# iot_demo_mote.net
KiCad netlist of a schematic drawn in EAGLE
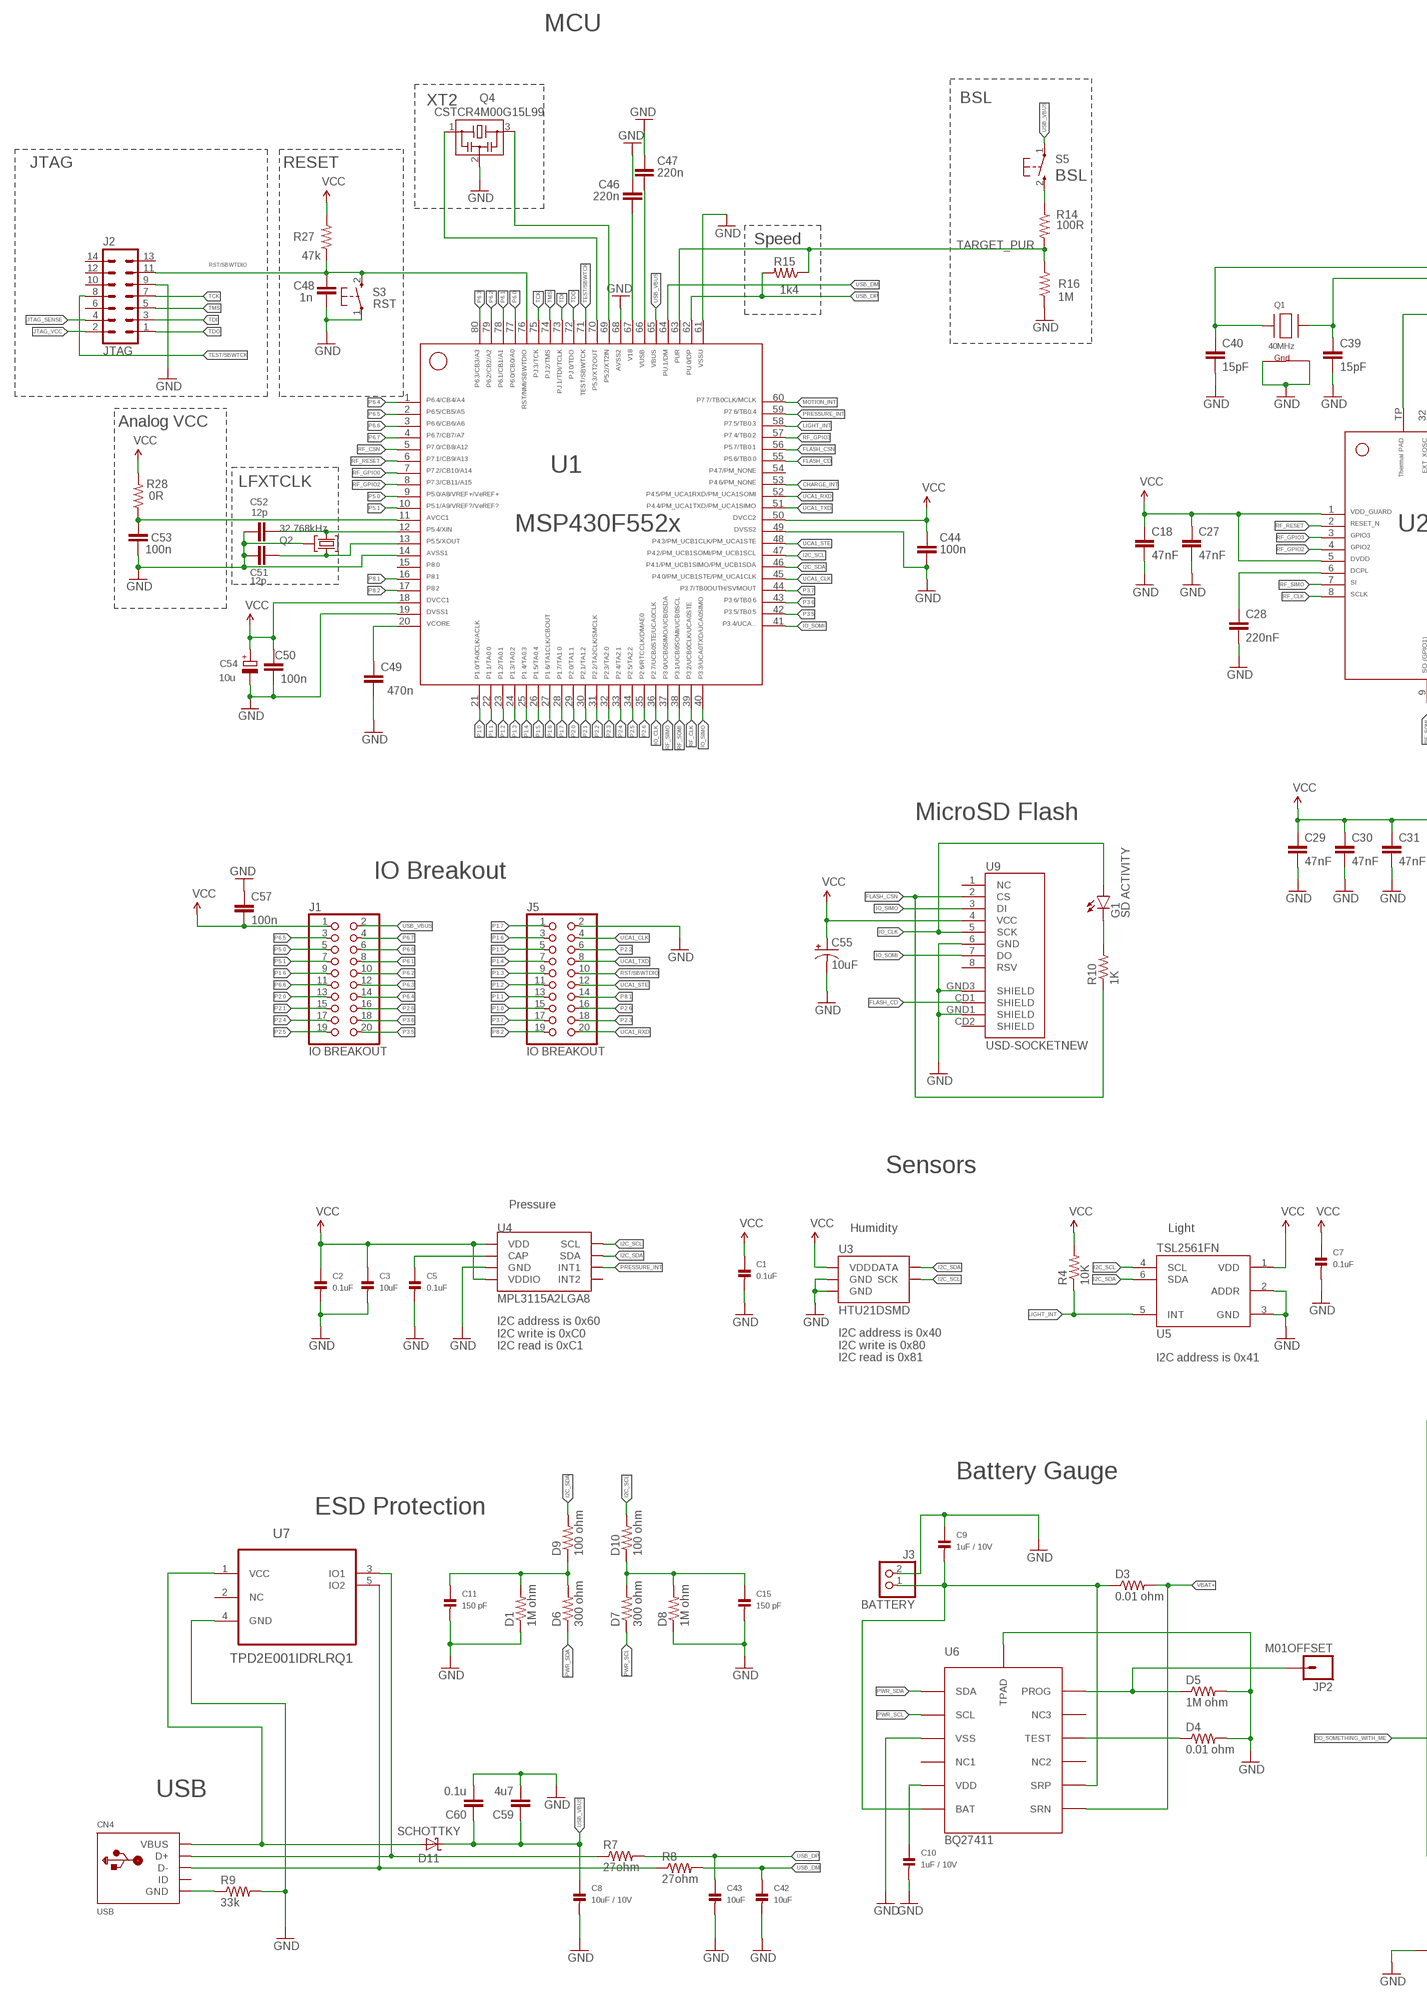
[diagram p0: schematic, sheet 1, part 1 of 2]
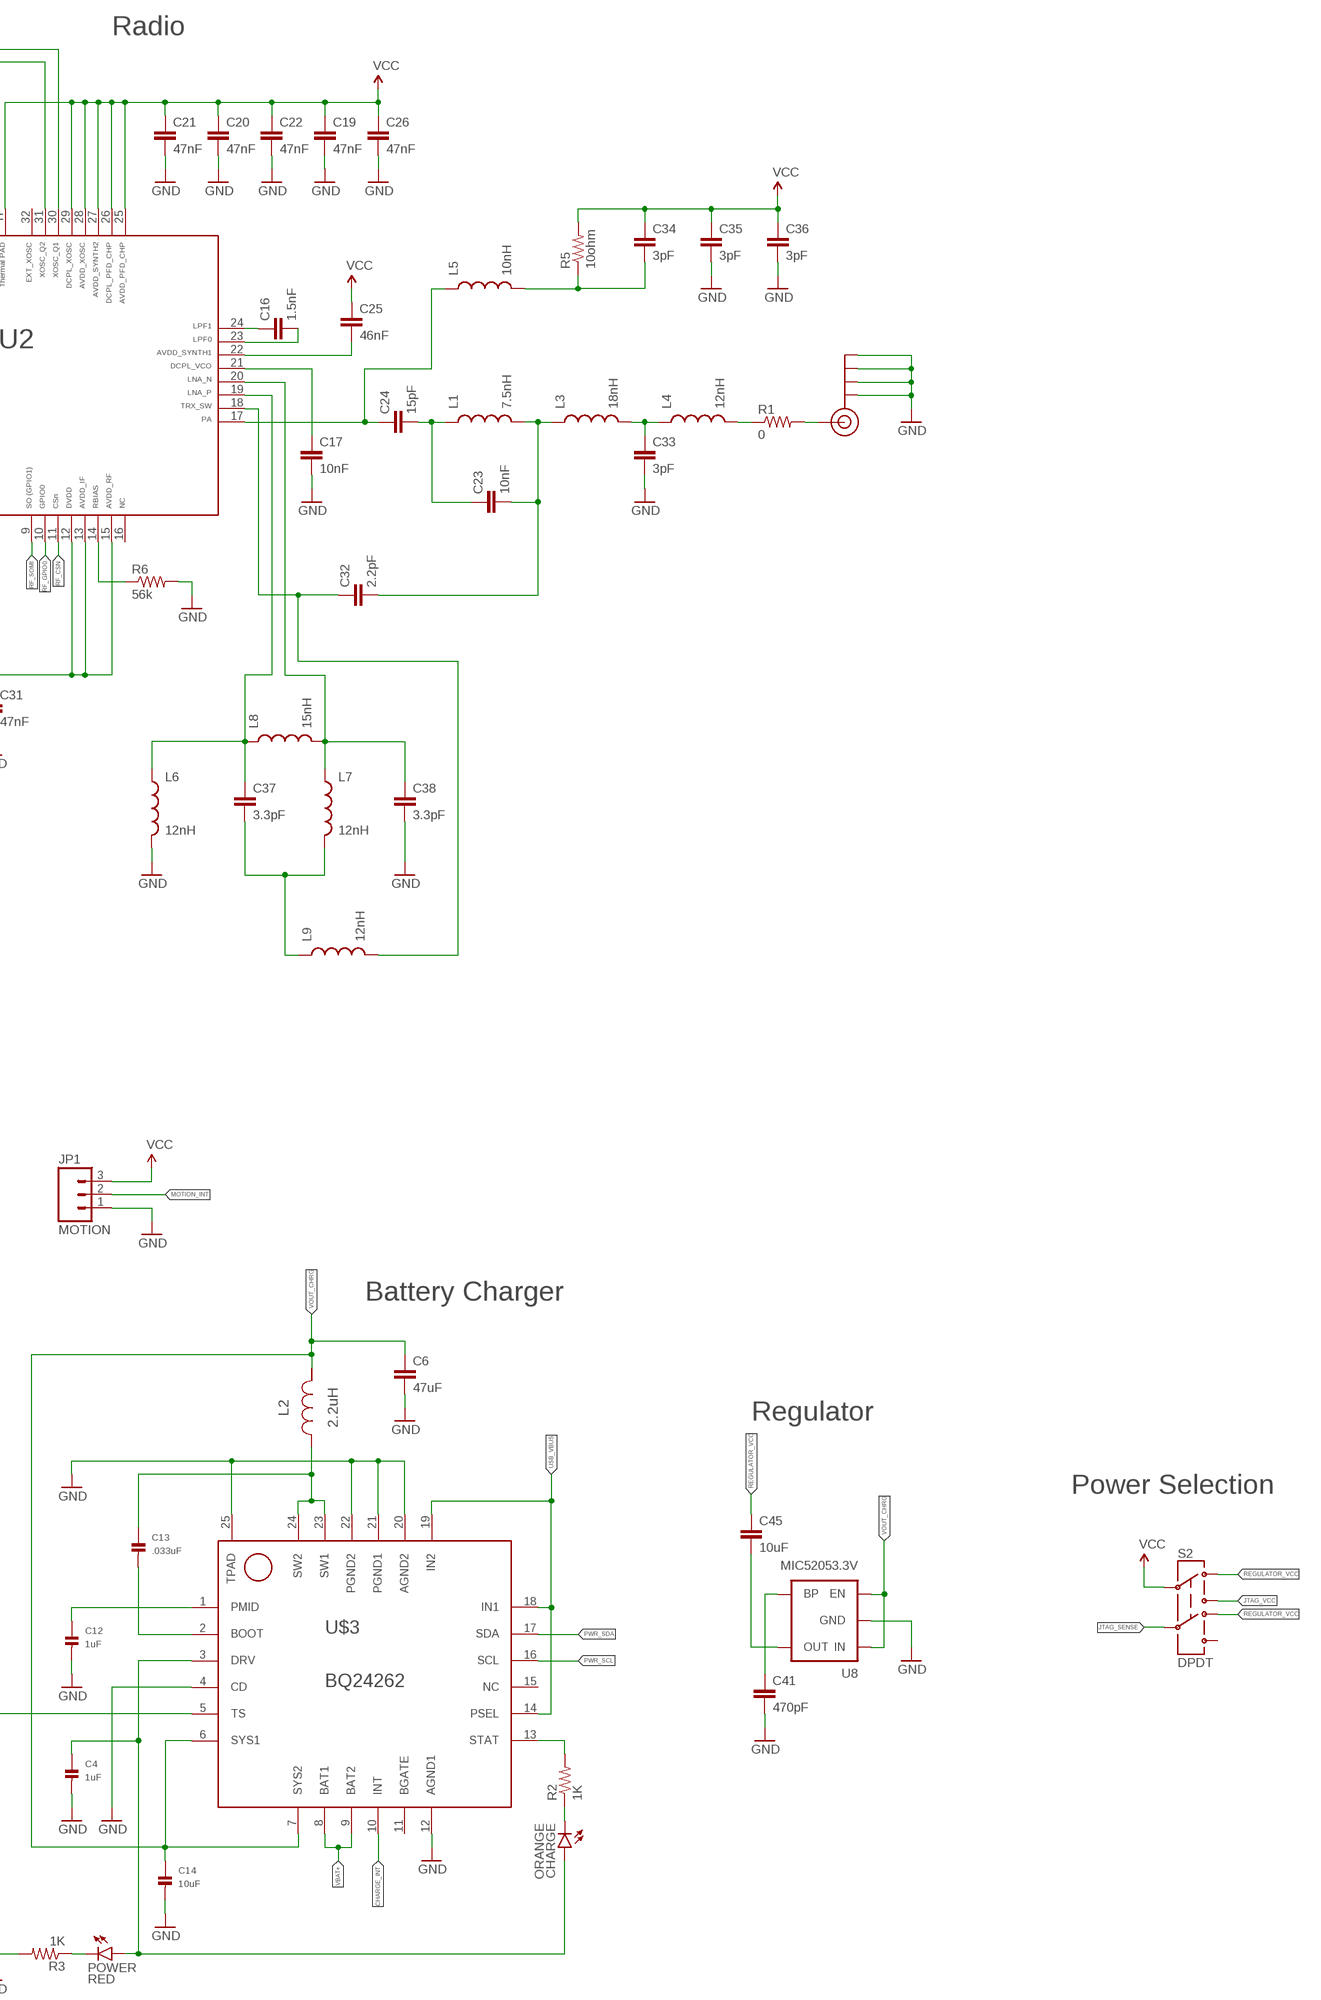
[diagram p1: schematic, sheet 1, part 2 of 2]

(export (version "E")
  (design (tool "Eeschema 10.0.6"))
  (components
    (comp (ref "C1")
      (value "0.1uF")
      (footprint "eagle-import:0603")
      (fields (field (name "MPN") "0603YC104JAT2A"))
      (libsource (lib "eagle-import") (part "CAP_CERAMIC0603"))
    )
    (comp (ref "C2")
      (value "0.1uF")
      (footprint "eagle-import:0603")
      (fields (field (name "MPN") "0603YC104JAT2A"))
      (libsource (lib "eagle-import") (part "CAP_CERAMIC0603"))
    )
    (comp (ref "C3")
      (value "10uF")
      (footprint "eagle-import:0603")
      (fields (field (name "MPN") "06035A100FAT2A"))
      (libsource (lib "eagle-import") (part "CAP_CERAMIC0603"))
    )
    (comp (ref "C4")
      (value "1uF")
      (footprint "eagle-import:0603")
      (fields (field (name "MPN") "06035A100FAT2A"))
      (libsource (lib "eagle-import") (part "CAP_CERAMIC0603"))
    )
    (comp (ref "C5")
      (value "0.1uF")
      (footprint "eagle-import:0603")
      (fields (field (name "MPN") "0603YC104JAT2A"))
      (libsource (lib "eagle-import") (part "CAP_CERAMIC0603"))
    )
    (comp (ref "C6")
      (value "47uF")
      (footprint "eagle-import:0402-CAP")
      (fields (field (name "MPN") "06035A100FAT2A"))
      (libsource (lib "eagle-import") (part "CAP0402-CAP"))
    )
    (comp (ref "C7")
      (value "0.1uF")
      (footprint "eagle-import:0603")
      (fields (field (name "MPN") "0603YC104JAT2A"))
      (libsource (lib "eagle-import") (part "CAP_CERAMIC0603"))
    )
    (comp (ref "C8")
      (value "10uF / 10V")
      (footprint "eagle-import:0603")
      (fields (field (name "MPN") "06035A100FAT2A"))
      (libsource (lib "eagle-import") (part "CAP_CERAMIC0603"))
    )
    (comp (ref "C9")
      (value "1uF / 10V")
      (footprint "eagle-import:0603")
      (fields (field (name "MPN") "06035A100FAT2A"))
      (libsource (lib "eagle-import") (part "CAP_CERAMIC0603"))
    )
    (comp (ref "C10")
      (value "1uF / 10V")
      (footprint "eagle-import:0603")
      (fields (field (name "MPN") "06035A100FAT2A"))
      (libsource (lib "eagle-import") (part "CAP_CERAMIC0603"))
    )
    (comp (ref "C11")
      (value "150 pF")
      (footprint "eagle-import:0603")
      (fields (field (name "MPN") "06035A100FAT2A"))
      (libsource (lib "eagle-import") (part "CAP_CERAMIC0603"))
    )
    (comp (ref "C12")
      (value "1uF")
      (footprint "eagle-import:0603")
      (fields (field (name "MPN") "06035A100FAT2A"))
      (libsource (lib "eagle-import") (part "CAP_CERAMIC0603"))
    )
    (comp (ref "C13")
      (value ".033uF")
      (footprint "eagle-import:0603")
      (fields (field (name "MPN") "06035A100FAT2A"))
      (libsource (lib "eagle-import") (part "CAP_CERAMIC0603"))
    )
    (comp (ref "C14")
      (value "10uF")
      (footprint "eagle-import:0603")
      (fields (field (name "MPN") "06035A100FAT2A"))
      (libsource (lib "eagle-import") (part "CAP_CERAMIC0603"))
    )
    (comp (ref "C15")
      (value "150 pF")
      (footprint "eagle-import:0603")
      (fields (field (name "MPN") "06035A100FAT2A"))
      (libsource (lib "eagle-import") (part "CAP_CERAMIC0603"))
    )
    (comp (ref "C16")
      (value "1.5nF")
      (footprint "eagle-import:0402-CAP")
      (fields (field (name "MPN") "0603YC104JAT2A"))
      (libsource (lib "eagle-import") (part "CAP0402-CAP"))
    )
    (comp (ref "C17")
      (value "10nF")
      (footprint "eagle-import:0402-CAP")
      (fields (field (name "MPN") "0603YC104JAT2A"))
      (libsource (lib "eagle-import") (part "CAP0402-CAP"))
    )
    (comp (ref "C18")
      (value "47nF")
      (footprint "eagle-import:0402-CAP")
      (fields (field (name "MPN") "0603YC104JAT2A"))
      (libsource (lib "eagle-import") (part "CAP0402-CAP"))
    )
    (comp (ref "C19")
      (value "47nF")
      (footprint "eagle-import:0402-CAP")
      (fields (field (name "MPN") "0603YC104JAT2A"))
      (libsource (lib "eagle-import") (part "CAP0402-CAP"))
    )
    (comp (ref "C20")
      (value "47nF")
      (footprint "eagle-import:0402-CAP")
      (fields (field (name "MPN") "0603YC104JAT2A"))
      (libsource (lib "eagle-import") (part "CAP0402-CAP"))
    )
    (comp (ref "C21")
      (value "47nF")
      (footprint "eagle-import:0402-CAP")
      (fields (field (name "MPN") "0603YC104JAT2A"))
      (libsource (lib "eagle-import") (part "CAP0402-CAP"))
    )
    (comp (ref "C22")
      (value "47nF")
      (footprint "eagle-import:0402-CAP")
      (fields (field (name "MPN") "0603YC104JAT2A"))
      (libsource (lib "eagle-import") (part "CAP0402-CAP"))
    )
    (comp (ref "C23")
      (value "10nF")
      (footprint "eagle-import:0402-CAP")
      (fields (field (name "MPN") "0603YC104JAT2A"))
      (libsource (lib "eagle-import") (part "CAP0402-CAP"))
    )
    (comp (ref "C24")
      (value "15pF")
      (footprint "eagle-import:0402-CAP")
      (fields (field (name "MPN") "0603YC104JAT2A"))
      (libsource (lib "eagle-import") (part "CAP0402-CAP"))
    )
    (comp (ref "C25")
      (value "46nF")
      (footprint "eagle-import:0402-CAP")
      (fields (field (name "MPN") "0603YC104JAT2A"))
      (libsource (lib "eagle-import") (part "CAP0402-CAP"))
    )
    (comp (ref "C26")
      (value "47nF")
      (footprint "eagle-import:0402-CAP")
      (fields (field (name "MPN") "0603YC104JAT2A"))
      (libsource (lib "eagle-import") (part "CAP0402-CAP"))
    )
    (comp (ref "C27")
      (value "47nF")
      (footprint "eagle-import:0402-CAP")
      (fields (field (name "MPN") "0603YC104JAT2A"))
      (libsource (lib "eagle-import") (part "CAP0402-CAP"))
    )
    (comp (ref "C28")
      (value "220nF")
      (footprint "eagle-import:0402-CAP")
      (fields (field (name "MPN") "0603YC104JAT2A"))
      (libsource (lib "eagle-import") (part "CAP0402-CAP"))
    )
    (comp (ref "C29")
      (value "47nF")
      (footprint "eagle-import:0402-CAP")
      (fields (field (name "MPN") "0603YC104JAT2A"))
      (libsource (lib "eagle-import") (part "CAP0402-CAP"))
    )
    (comp (ref "C30")
      (value "47nF")
      (footprint "eagle-import:0402-CAP")
      (fields (field (name "MPN") "0603YC104JAT2A"))
      (libsource (lib "eagle-import") (part "CAP0402-CAP"))
    )
    (comp (ref "C31")
      (value "47nF")
      (footprint "eagle-import:0402-CAP")
      (fields (field (name "MPN") "0603YC104JAT2A"))
      (libsource (lib "eagle-import") (part "CAP0402-CAP"))
    )
    (comp (ref "C32")
      (value "2.2pF")
      (footprint "eagle-import:0402-CAP")
      (fields (field (name "MPN") "0603YC104JAT2A"))
      (libsource (lib "eagle-import") (part "CAP0402-CAP"))
    )
    (comp (ref "C33")
      (value "3pF")
      (footprint "eagle-import:0402-CAP")
      (fields (field (name "MPN") "0603YC104JAT2A"))
      (libsource (lib "eagle-import") (part "CAP0402-CAP"))
    )
    (comp (ref "C34")
      (value "3pF")
      (footprint "eagle-import:0402-CAP")
      (fields (field (name "MPN") "0603YC104JAT2A"))
      (libsource (lib "eagle-import") (part "CAP0402-CAP"))
    )
    (comp (ref "C35")
      (value "3pF")
      (footprint "eagle-import:0402-CAP")
      (fields (field (name "MPN") "0603YC104JAT2A"))
      (libsource (lib "eagle-import") (part "CAP0402-CAP"))
    )
    (comp (ref "C36")
      (value "3pF")
      (footprint "eagle-import:0402-CAP")
      (fields (field (name "MPN") "0603YC104JAT2A"))
      (libsource (lib "eagle-import") (part "CAP0402-CAP"))
    )
    (comp (ref "C37")
      (value "3.3pF")
      (footprint "eagle-import:0402-CAP")
      (fields (field (name "MPN") "0603YC104JAT2A"))
      (libsource (lib "eagle-import") (part "CAP0402-CAP"))
    )
    (comp (ref "C38")
      (value "3.3pF")
      (footprint "eagle-import:0402-CAP")
      (fields (field (name "MPN") "0603YC104JAT2A"))
      (libsource (lib "eagle-import") (part "CAP0402-CAP"))
    )
    (comp (ref "C39")
      (value "15pF")
      (footprint "eagle-import:0402-CAP")
      (fields (field (name "MPN") "0603YC104JAT2A"))
      (libsource (lib "eagle-import") (part "CAP0402-CAP"))
    )
    (comp (ref "C40")
      (value "15pF")
      (footprint "eagle-import:0402-CAP")
      (fields (field (name "MPN") "0603YC104JAT2A"))
      (libsource (lib "eagle-import") (part "CAP0402-CAP"))
    )
    (comp (ref "C41")
      (value "470pF")
      (footprint "eagle-import:0402-CAP")
      (fields (field (name "MPN") "06035A100FAT2A"))
      (libsource (lib "eagle-import") (part "CAP0402-CAP"))
    )
    (comp (ref "C42")
      (value "10uF")
      (footprint "eagle-import:0603")
      (fields (field (name "MPN") "06035A100FAT2A"))
      (libsource (lib "eagle-import") (part "CAP_CERAMIC0603"))
    )
    (comp (ref "C43")
      (value "10uF")
      (footprint "eagle-import:0603")
      (fields (field (name "MPN") "06035A100FAT2A"))
      (libsource (lib "eagle-import") (part "CAP_CERAMIC0603"))
    )
    (comp (ref "C44")
      (value "100n")
      (footprint "eagle-import:C0402")
      (libsource (lib "eagle-import") (part "C-EUC0402"))
    )
    (comp (ref "C45")
      (value "10uF")
      (footprint "eagle-import:0402-CAP")
      (fields (field (name "MPN") "06035A100FAT2A"))
      (libsource (lib "eagle-import") (part "CAP0402-CAP"))
    )
    (comp (ref "C46")
      (value "220n")
      (footprint "eagle-import:C0402")
      (libsource (lib "eagle-import") (part "C-EUC0402"))
    )
    (comp (ref "C47")
      (value "220n")
      (footprint "eagle-import:C0402")
      (libsource (lib "eagle-import") (part "C-EUC0402"))
    )
    (comp (ref "C48")
      (value "1n")
      (footprint "eagle-import:C0402")
      (libsource (lib "eagle-import") (part "C-EUC0402"))
    )
    (comp (ref "C49")
      (value "470n")
      (footprint "eagle-import:C0402")
      (libsource (lib "eagle-import") (part "C-EUC0402"))
    )
    (comp (ref "C50")
      (value "100n")
      (footprint "eagle-import:C0402")
      (libsource (lib "eagle-import") (part "C-EUC0402"))
    )
    (comp (ref "C51")
      (value "12p")
      (footprint "eagle-import:C0402")
      (libsource (lib "eagle-import") (part "C-EUC0402"))
    )
    (comp (ref "C52")
      (value "12p")
      (footprint "eagle-import:C0402")
      (libsource (lib "eagle-import") (part "C-EUC0402"))
    )
    (comp (ref "C53")
      (value "100n")
      (footprint "eagle-import:C0402")
      (libsource (lib "eagle-import") (part "C-EUC0402"))
    )
    (comp (ref "C54")
      (value "10u")
      (footprint "eagle-import:A_3216-18R")
      (libsource (lib "eagle-import") (part "CPOL-EUA/3216-18R"))
    )
    (comp (ref "C55")
      (value "10uF")
      (footprint "eagle-import:A_3216-18R")
      (libsource (lib "eagle-import") (part "CPOL-USA/3216-18R"))
    )
    (comp (ref "C57")
      (value "100n")
      (footprint "eagle-import:C0402")
      (libsource (lib "eagle-import") (part "C-EUC0402"))
    )
    (comp (ref "C59")
      (value "4u7")
      (footprint "eagle-import:C0603")
      (libsource (lib "eagle-import") (part "C-EUC0603"))
    )
    (comp (ref "C60")
      (value "0.1u")
      (footprint "eagle-import:C0603")
      (libsource (lib "eagle-import") (part "C-EUC0603"))
    )
    (comp (ref "CHARGE")
      (value "ORANGE")
      (footprint "eagle-import:LED-0603")
      (libsource (lib "eagle-import") (part "LED0603"))
    )
    (comp (ref "CN4")
      (value "USB")
      (footprint "eagle-import:USB-MINIB")
      (libsource (lib "eagle-import") (part "USBMINIB"))
    )
    (comp (ref "D1")
      (value "1M ohm")
      (footprint "eagle-import:R0402")
      (libsource (lib "eagle-import") (part "R-US_R0402"))
    )
    (comp (ref "D3")
      (value "0.01 ohm")
      (footprint "eagle-import:R0402")
      (libsource (lib "eagle-import") (part "R-US_R0402"))
    )
    (comp (ref "D4")
      (value "0.01 ohm")
      (footprint "eagle-import:R0402")
      (libsource (lib "eagle-import") (part "R-US_R0402"))
    )
    (comp (ref "D5")
      (value "1M ohm")
      (footprint "eagle-import:R0402")
      (libsource (lib "eagle-import") (part "R-US_R0402"))
    )
    (comp (ref "D6")
      (value "300 ohm")
      (footprint "eagle-import:R0402")
      (libsource (lib "eagle-import") (part "R-US_R0402"))
    )
    (comp (ref "D7")
      (value "300 ohm")
      (footprint "eagle-import:R0402")
      (libsource (lib "eagle-import") (part "R-US_R0402"))
    )
    (comp (ref "D8")
      (value "1M ohm")
      (footprint "eagle-import:R0402")
      (libsource (lib "eagle-import") (part "R-US_R0402"))
    )
    (comp (ref "D9")
      (value "100 ohm")
      (footprint "eagle-import:R0402")
      (libsource (lib "eagle-import") (part "R-US_R0402"))
    )
    (comp (ref "D10")
      (value "100 ohm")
      (footprint "eagle-import:R0402")
      (libsource (lib "eagle-import") (part "R-US_R0402"))
    )
    (comp (ref "D11")
      (value "SCHOTTKY")
      (footprint "eagle-import:MINIMELF")
      (libsource (lib "eagle-import") (part "SCHOTTKY-MINI-MELF"))
    )
    (comp (ref "G1")
      (value "SD ACTIVITY")
      (footprint "eagle-import:LED-0603")
      (libsource (lib "eagle-import") (part "LED0603"))
    )
    (comp (ref "J$1")
      (value "SMA_EDGE")
      (footprint "eagle-import:SMA-EDGE")
      (libsource (lib "eagle-import") (part "SMA_EDGE"))
    )
    (comp (ref "J1")
      (value "IO BREAKOUT")
      (footprint "eagle-import:2X10")
      (libsource (lib "eagle-import") (part "PINHD-2X10"))
    )
    (comp (ref "J2")
      (value "JTAG")
      (footprint "eagle-import:ML14")
      (libsource (lib "eagle-import") (part "ML14"))
    )
    (comp (ref "J3")
      (value "BATTERY")
      (footprint "eagle-import:JST-PH-2-SMT-RA")
      (libsource (lib "eagle-import") (part "JST_2PIN-SMT-RA"))
    )
    (comp (ref "J5")
      (value "IO BREAKOUT")
      (footprint "eagle-import:2X10")
      (libsource (lib "eagle-import") (part "PINHD-2X10"))
    )
    (comp (ref "JP1")
      (value "MOTION")
      (footprint "eagle-import:JST-3-PTH-VERT")
      (libsource (lib "eagle-import") (part "M03JST-PTH-VERT"))
    )
    (comp (ref "JP2")
      (value "M01OFFSET")
      (footprint "eagle-import:1X01_OFFSET")
      (libsource (lib "eagle-import") (part "M01OFFSET"))
    )
    (comp (ref "L1")
      (value "7.5nH")
      (footprint "eagle-import:C0402")
      (libsource (lib "eagle-import") (part "INDUCTOR0402"))
    )
    (comp (ref "L2")
      (value "2.2uH")
      (footprint "eagle-import:SDR0403")
      (fields (field (name "MANUFACTURER_PART_NUMBER") "SDR0403-2R2ML"))
      (libsource (lib "eagle-import") (part "SDR0403-2R2MLSDR0403-2R2ML"))
    )
    (comp (ref "L3")
      (value "18nH")
      (footprint "eagle-import:C0402")
      (libsource (lib "eagle-import") (part "INDUCTOR0402"))
    )
    (comp (ref "L4")
      (value "12nH")
      (footprint "eagle-import:C0402")
      (libsource (lib "eagle-import") (part "INDUCTOR0402"))
    )
    (comp (ref "L5")
      (value "10nH")
      (footprint "eagle-import:C0402")
      (libsource (lib "eagle-import") (part "INDUCTOR0402"))
    )
    (comp (ref "L6")
      (value "12nH")
      (footprint "eagle-import:C0402")
      (libsource (lib "eagle-import") (part "INDUCTOR0402"))
    )
    (comp (ref "L7")
      (value "12nH")
      (footprint "eagle-import:C0402")
      (libsource (lib "eagle-import") (part "INDUCTOR0402"))
    )
    (comp (ref "L8")
      (value "15nH")
      (footprint "eagle-import:C0402")
      (libsource (lib "eagle-import") (part "INDUCTOR0402"))
    )
    (comp (ref "L9")
      (value "12nH")
      (footprint "eagle-import:C0402")
      (libsource (lib "eagle-import") (part "INDUCTOR0402"))
    )
    (comp (ref "POWER")
      (value "RED")
      (footprint "eagle-import:LED-0603")
      (libsource (lib "eagle-import") (part "LED0603"))
    )
    (comp (ref "Q1")
      (value "40MHz")
      (footprint "eagle-import:NX3225")
      (libsource (lib "eagle-import") (part "XTAL-4-3225"))
    )
    (comp (ref "Q2")
      (value "32.768kHz")
      (footprint "eagle-import:MS3V-T1R")
      (libsource (lib "eagle-import") (part "MS3V-T1R"))
    )
    (comp (ref "Q4")
      (value "CSTCR4M00G15L99")
      (footprint "eagle-import:MURATA-FILTER_CSTCR")
      (fields (field (name "MPN") "CSTCR6M00G53-R0"))
      (libsource (lib "eagle-import") (part "MURATA-FILTER_CSTCR6M00G53Z"))
    )
    (comp (ref "R1")
      (value "0")
      (footprint "eagle-import:0402-RES")
      (libsource (lib "eagle-import") (part "RESISTOR0402-RES"))
    )
    (comp (ref "R2")
      (value "1K")
      (footprint "eagle-import:R0402")
      (libsource (lib "eagle-import") (part "R-US_R0402"))
    )
    (comp (ref "R3")
      (value "1K")
      (footprint "eagle-import:R0402")
      (libsource (lib "eagle-import") (part "R-US_R0402"))
    )
    (comp (ref "R4")
      (value "10K")
      (footprint "eagle-import:R0402")
      (fields (field (name "MPN") "ERJ-P03F1002V"))
      (libsource (lib "eagle-import") (part "R-US_R0402"))
    )
    (comp (ref "R5")
      (value "10ohm")
      (footprint "eagle-import:0402-RES")
      (libsource (lib "eagle-import") (part "RESISTOR0402-RES"))
    )
    (comp (ref "R6")
      (value "56k")
      (footprint "eagle-import:0402-RES")
      (libsource (lib "eagle-import") (part "RESISTOR0402-RES"))
    )
    (comp (ref "R7")
      (value "27ohm")
      (footprint "eagle-import:0402-RES")
      (libsource (lib "eagle-import") (part "RESISTOR0402-RES"))
    )
    (comp (ref "R8")
      (value "27ohm")
      (footprint "eagle-import:0402-RES")
      (libsource (lib "eagle-import") (part "RESISTOR0402-RES"))
    )
    (comp (ref "R9")
      (value "33k")
      (footprint "eagle-import:0402-RES")
      (libsource (lib "eagle-import") (part "RESISTOR0402-RES"))
    )
    (comp (ref "R10")
      (value "1K")
      (footprint "eagle-import:0402-RES")
      (libsource (lib "eagle-import") (part "RESISTOR0402-RES"))
    )
    (comp (ref "R14")
      (value "100R")
      (footprint "eagle-import:R0402")
      (libsource (lib "eagle-import") (part "R-US_R0402"))
    )
    (comp (ref "R15")
      (value "1k4")
      (footprint "eagle-import:R0402")
      (libsource (lib "eagle-import") (part "R-US_R0402"))
    )
    (comp (ref "R16")
      (value "1M")
      (footprint "eagle-import:R0402")
      (libsource (lib "eagle-import") (part "R-US_R0402"))
    )
    (comp (ref "R27")
      (value "47k")
      (footprint "eagle-import:R0402")
      (libsource (lib "eagle-import") (part "R-US_R0402"))
    )
    (comp (ref "R28")
      (value "0R")
      (footprint "eagle-import:R0402")
      (libsource (lib "eagle-import") (part "R-US_R0402"))
    )
    (comp (ref "S2")
      (value "DPDT")
      (footprint "eagle-import:AYZ0202")
      (libsource (lib "eagle-import") (part "SWITCH-DPDTAYZ0202"))
    )
    (comp (ref "S3")
      (value "RST")
      (footprint "eagle-import:PBTH")
      (libsource (lib "eagle-import") (part "PB"))
    )
    (comp (ref "S5")
      (value "BSL")
      (footprint "eagle-import:PBTH")
      (libsource (lib "eagle-import") (part "PB"))
    )
    (comp (ref "U$3")
      (value "BQ24262")
      (footprint "eagle-import:QFN50P400X400X80-25N")
      (libsource (lib "eagle-import") (part "BQ24262"))
    )
    (comp (ref "U1")
      (value "MSP430F5529IPNR")
      (footprint "eagle-import:PN80")
      (libsource (lib "eagle-import") (part "F552X---PN80"))
    )
    (comp (ref "U2")
      (value "CC1200")
      (footprint "eagle-import:RHB32")
      (libsource (lib "eagle-import") (part "CC1200"))
    )
    (comp (ref "U3")
      (value "HTU21DSMD")
      (footprint "eagle-import:HTU21D")
      (fields (field (name "MPN") "HTU21D"))
      (libsource (lib "eagle-import") (part "HTU21DSMD"))
    )
    (comp (ref "U4")
      (value "MPL3115A2LGA8")
      (footprint "eagle-import:LGA8")
      (fields (field (name "MPN") "MPL3115A2"))
      (libsource (lib "eagle-import") (part "MPL3115A2LGA8"))
    )
    (comp (ref "U5")
      (value "TSL2561FN")
      (footprint "eagle-import:FN-6")
      (fields (field (name "MPN") "TSL2561T"))
      (libsource (lib "eagle-import") (part "TSL2561FN"))
    )
    (comp (ref "U6")
      (value "BQ27411")
      (footprint "eagle-import:VSON40P400X400X12")
      (libsource (lib "eagle-import") (part "BQ27411"))
    )
    (comp (ref "U7")
      (value "TPD2E001IDRLRQ1")
      (footprint "eagle-import:SOT50P160X60-5N")
      (libsource (lib "eagle-import") (part "TPD2E001IDRLRQ1"))
    )
    (comp (ref "U8")
      (value "MIC52053.3V")
      (footprint "eagle-import:SOT23-5")
      (libsource (lib "eagle-import") (part "MIC52053.3V"))
    )
    (comp (ref "U9")
      (value "USD-SOCKETNEW")
      (footprint "eagle-import:MICRO-SD-SOCKET-PP")
      (libsource (lib "eagle-import") (part "USD-SOCKETNEW"))
    )
  )
  (nets
    (net (code "1") (name "/TARGET_PUR") (class "Default")
      (node (ref "R14") (pin "2") (pinfunction "2_2") (pintype "passive"))
      (node (ref "R15") (pin "1") (pinfunction "1_1") (pintype "passive"))
      (node (ref "R16") (pin "2") (pinfunction "2_2") (pintype "passive"))
      (node (ref "U1") (pin "63") (pinfunction "63_63") (pintype "bidirectional"))
    )
    (net (code "2") (name "CHARGE_INT") (class "Default")
      (node (ref "U$3") (pin "10") (pinfunction "INT_10") (pintype "bidirectional"))
      (node (ref "U1") (pin "53") (pinfunction "53_53") (pintype "bidirectional"))
    )
    (net (code "3") (name "DO_SOMETHING_WITH_ME") (class "Default")
      (node (ref "U$3") (pin "5") (pinfunction "TS_5") (pintype "bidirectional"))
    )
    (net (code "4") (name "FLASH_CD") (class "Default")
      (node (ref "U1") (pin "55") (pinfunction "55_55") (pintype "bidirectional"))
      (node (ref "U9") (pin "CD1") (pinfunction "SHIELD_CD1") (pintype "bidirectional"))
    )
    (net (code "5") (name "FLASH_CSN") (class "Default")
      (node (ref "R10") (pin "1") (pinfunction "1_1") (pintype "passive"))
      (node (ref "U1") (pin "56") (pinfunction "56_56") (pintype "bidirectional"))
      (node (ref "U9") (pin "2") (pinfunction "CS_2") (pintype "bidirectional"))
    )
    (net (code "6") (name "GND") (class "Default")
      (node (ref "C1") (pin "2") (pinfunction "P$2_2") (pintype "passive"))
      (node (ref "C10") (pin "2") (pinfunction "P$2_2") (pintype "passive"))
      (node (ref "C11") (pin "2") (pinfunction "P$2_2") (pintype "passive"))
      (node (ref "C12") (pin "2") (pinfunction "P$2_2") (pintype "passive"))
      (node (ref "C14") (pin "2") (pinfunction "P$2_2") (pintype "passive"))
      (node (ref "C15") (pin "2") (pinfunction "P$2_2") (pintype "passive"))
      (node (ref "C17") (pin "2") (pinfunction "2_2") (pintype "passive"))
      (node (ref "C18") (pin "2") (pinfunction "2_2") (pintype "passive"))
      (node (ref "C19") (pin "2") (pinfunction "2_2") (pintype "passive"))
      (node (ref "C2") (pin "2") (pinfunction "P$2_2") (pintype "passive"))
      (node (ref "C20") (pin "2") (pinfunction "2_2") (pintype "passive"))
      (node (ref "C21") (pin "2") (pinfunction "2_2") (pintype "passive"))
      (node (ref "C22") (pin "2") (pinfunction "2_2") (pintype "passive"))
      (node (ref "C26") (pin "2") (pinfunction "2_2") (pintype "passive"))
      (node (ref "C27") (pin "2") (pinfunction "2_2") (pintype "passive"))
      (node (ref "C28") (pin "2") (pinfunction "2_2") (pintype "passive"))
      (node (ref "C29") (pin "2") (pinfunction "2_2") (pintype "passive"))
      (node (ref "C3") (pin "2") (pinfunction "P$2_2") (pintype "passive"))
      (node (ref "C30") (pin "2") (pinfunction "2_2") (pintype "passive"))
      (node (ref "C31") (pin "2") (pinfunction "2_2") (pintype "passive"))
      (node (ref "C33") (pin "2") (pinfunction "2_2") (pintype "passive"))
      (node (ref "C35") (pin "2") (pinfunction "2_2") (pintype "passive"))
      (node (ref "C36") (pin "2") (pinfunction "2_2") (pintype "passive"))
      (node (ref "C38") (pin "2") (pinfunction "2_2") (pintype "passive"))
      (node (ref "C39") (pin "2") (pinfunction "2_2") (pintype "passive"))
      (node (ref "C4") (pin "2") (pinfunction "P$2_2") (pintype "passive"))
      (node (ref "C40") (pin "2") (pinfunction "2_2") (pintype "passive"))
      (node (ref "C41") (pin "2") (pinfunction "2_2") (pintype "passive"))
      (node (ref "C42") (pin "2") (pinfunction "P$2_2") (pintype "passive"))
      (node (ref "C43") (pin "2") (pinfunction "P$2_2") (pintype "passive"))
      (node (ref "C44") (pin "2") (pinfunction "2_2") (pintype "passive"))
      (node (ref "C46") (pin "2") (pinfunction "2_2") (pintype "passive"))
      (node (ref "C47") (pin "2") (pinfunction "2_2") (pintype "passive"))
      (node (ref "C48") (pin "2") (pinfunction "2_2") (pintype "passive"))
      (node (ref "C49") (pin "1") (pinfunction "1_1") (pintype "passive"))
      (node (ref "C5") (pin "2") (pinfunction "P$2_2") (pintype "passive"))
      (node (ref "C50") (pin "1") (pinfunction "1_1") (pintype "passive"))
      (node (ref "C51") (pin "1") (pinfunction "1_1") (pintype "passive"))
      (node (ref "C52") (pin "1") (pinfunction "1_1") (pintype "passive"))
      (node (ref "C53") (pin "2") (pinfunction "2_2") (pintype "passive"))
      (node (ref "C54") (pin "-") (pinfunction "-_-") (pintype "passive"))
      (node (ref "C55") (pin "-") (pinfunction "-_-") (pintype "passive"))
      (node (ref "C57") (pin "1") (pinfunction "1_1") (pintype "passive"))
      (node (ref "C59") (pin "2") (pinfunction "2_2") (pintype "passive"))
      (node (ref "C6") (pin "2") (pinfunction "2_2") (pintype "passive"))
      (node (ref "C60") (pin "2") (pinfunction "2_2") (pintype "passive"))
      (node (ref "C7") (pin "2") (pinfunction "P$2_2") (pintype "passive"))
      (node (ref "C8") (pin "2") (pinfunction "P$2_2") (pintype "passive"))
      (node (ref "C9") (pin "1") (pinfunction "P$1_1") (pintype "passive"))
      (node (ref "D1") (pin "1") (pinfunction "1_1") (pintype "passive"))
      (node (ref "D4") (pin "2") (pinfunction "2_2") (pintype "passive"))
      (node (ref "D5") (pin "2") (pinfunction "2_2") (pintype "passive"))
      (node (ref "D8") (pin "1") (pinfunction "1_1") (pintype "passive"))
      (node (ref "J$1") (pin "GND@0") (pinfunction "GND_GND@0") (pintype "bidirectional"))
      (node (ref "J$1") (pin "GND@1") (pinfunction "GND_GND@1") (pintype "bidirectional"))
      (node (ref "J$1") (pin "GND@2") (pinfunction "GND_GND@2") (pintype "bidirectional"))
      (node (ref "J$1") (pin "GND@3") (pinfunction "GND_GND@3") (pintype "bidirectional"))
      (node (ref "J2") (pin "9") (pinfunction "9_9") (pintype "passive"))
      (node (ref "J3") (pin "2") (pinfunction "1_2") (pintype "passive"))
      (node (ref "J5") (pin "2") (pinfunction "2_2") (pintype "passive"))
      (node (ref "JP1") (pin "1") (pinfunction "1_1") (pintype "passive"))
      (node (ref "L6") (pin "2") (pinfunction "2_2") (pintype "passive"))
      (node (ref "Q1") (pin "2") (pinfunction "G2_2") (pintype "power_in"))
      (node (ref "Q1") (pin "4") (pinfunction "G1_4") (pintype "power_in"))
      (node (ref "Q2") (pin "P3") (pinfunction "GND_P3") (pintype "power_in"))
      (node (ref "Q4") (pin "2") (pinfunction "2_2") (pintype "passive"))
      (node (ref "R16") (pin "1") (pinfunction "1_1") (pintype "passive"))
      (node (ref "R3") (pin "2") (pinfunction "2_2") (pintype "passive"))
      (node (ref "R6") (pin "2") (pinfunction "2_2") (pintype "passive"))
      (node (ref "R9") (pin "2") (pinfunction "2_2") (pintype "passive"))
      (node (ref "S3") (pin "1") (pinfunction "P_1") (pintype "passive"))
      (node (ref "U$3") (pin "12") (pinfunction "AGND1_12") (pintype "bidirectional"))
      (node (ref "U$3") (pin "20") (pinfunction "AGND2_20") (pintype "bidirectional"))
      (node (ref "U$3") (pin "21") (pinfunction "PGND1_21") (pintype "bidirectional"))
      (node (ref "U$3") (pin "22") (pinfunction "PGND2_22") (pintype "bidirectional"))
      (node (ref "U$3") (pin "25") (pinfunction "TPAD_25") (pintype "bidirectional"))
      (node (ref "U$3") (pin "4") (pinfunction "CD_4") (pintype "bidirectional"))
      (node (ref "U1") (pin "14") (pinfunction "14_14") (pintype "power_in"))
      (node (ref "U1") (pin "19") (pinfunction "19_19") (pintype "power_in"))
      (node (ref "U1") (pin "49") (pinfunction "49_49") (pintype "power_in"))
      (node (ref "U1") (pin "61") (pinfunction "61_61") (pintype "power_in"))
      (node (ref "U1") (pin "68") (pinfunction "68_68") (pintype "power_in"))
      (node (ref "U3") (pin "7") (pinfunction "GND_7") (pintype "power_in"))
      (node (ref "U3") (pin "GND") (pinfunction "GND_GND") (pintype "power_in"))
      (node (ref "U4") (pin "3") (pinfunction "GND_3") (pintype "power_in"))
      (node (ref "U5") (pin "2") (pinfunction "ADDR_2") (pintype "input"))
      (node (ref "U5") (pin "3") (pinfunction "GND_3") (pintype "power_in"))
      (node (ref "U6") (pin "P$13") (pinfunction "TPAD_P$13") (pintype "bidirectional"))
      (node (ref "U6") (pin "P$3") (pinfunction "VSS_P$3") (pintype "bidirectional"))
      (node (ref "U7") (pin "4") (pinfunction "GND_4") (pintype "passive"))
      (node (ref "U8") (pin "2") (pinfunction "GND_2") (pintype "input"))
      (node (ref "U9") (pin "6") (pinfunction "GND_6") (pintype "bidirectional"))
      (node (ref "U9") (pin "GND1") (pinfunction "SHIELD_GND1") (pintype "bidirectional"))
      (node (ref "U9") (pin "GND3") (pinfunction "SHIELD_GND3") (pintype "bidirectional"))
    )
    (net (code "7") (name "I2C_SCL") (class "Default")
      (node (ref "D10") (pin "2") (pinfunction "2_2") (pintype "passive"))
      (node (ref "U1") (pin "47") (pinfunction "47_47") (pintype "bidirectional"))
      (node (ref "U3") (pin "SCK") (pinfunction "SCK_SCK") (pintype "input"))
      (node (ref "U4") (pin "8") (pinfunction "SCL_8") (pintype "bidirectional"))
      (node (ref "U5") (pin "4") (pinfunction "SCL_4") (pintype "input"))
    )
    (net (code "8") (name "I2C_SDA") (class "Default")
      (node (ref "D9") (pin "2") (pinfunction "2_2") (pintype "passive"))
      (node (ref "U1") (pin "46") (pinfunction "46_46") (pintype "bidirectional"))
      (node (ref "U3") (pin "DATA") (pinfunction "DATA_DATA") (pintype "bidirectional"))
      (node (ref "U4") (pin "7") (pinfunction "SDA_7") (pintype "bidirectional"))
      (node (ref "U5") (pin "6") (pinfunction "SDA_6") (pintype "bidirectional"))
    )
    (net (code "9") (name "IO_CLK") (class "Default")
      (node (ref "G1") (pin "A") (pinfunction "A_A") (pintype "passive"))
      (node (ref "U1") (pin "36") (pinfunction "36_36") (pintype "bidirectional"))
      (node (ref "U9") (pin "5") (pinfunction "SCK_5") (pintype "bidirectional"))
    )
    (net (code "10") (name "IO_SIMO") (class "Default")
      (node (ref "U1") (pin "40") (pinfunction "40_40") (pintype "bidirectional"))
      (node (ref "U9") (pin "3") (pinfunction "DI_3") (pintype "bidirectional"))
    )
    (net (code "11") (name "IO_SOMI") (class "Default")
      (node (ref "U1") (pin "41") (pinfunction "41_41") (pintype "bidirectional"))
      (node (ref "U9") (pin "7") (pinfunction "DO_7") (pintype "bidirectional"))
    )
    (net (code "12") (name "JTAG_SENSE") (class "Default")
      (node (ref "J2") (pin "4") (pinfunction "4_4") (pintype "passive"))
      (node (ref "S2") (pin "5") (pinfunction "5_5") (pintype "bidirectional"))
    )
    (net (code "13") (name "JTAG_VCC") (class "Default")
      (node (ref "J2") (pin "2") (pinfunction "2_2") (pintype "passive"))
      (node (ref "S2") (pin "3") (pinfunction "3_3") (pintype "bidirectional"))
    )
    (net (code "14") (name "LIGHT_INT") (class "Default")
      (node (ref "R4") (pin "1") (pinfunction "1_1") (pintype "passive"))
      (node (ref "U1") (pin "58") (pinfunction "58_58") (pintype "bidirectional"))
      (node (ref "U5") (pin "5") (pinfunction "INT_5") (pintype "output"))
    )
    (net (code "15") (name "MOTION_INT") (class "Default")
      (node (ref "JP1") (pin "2") (pinfunction "2_2") (pintype "passive"))
      (node (ref "U1") (pin "60") (pinfunction "60_60") (pintype "bidirectional"))
    )
    (net (code "16") (name "Net-(C4-P$1)") (class "Default")
      (node (ref "C4") (pin "1") (pinfunction "P$1_1") (pintype "passive"))
      (node (ref "CHARGE") (pin "A") (pinfunction "A_A") (pintype "passive"))
      (node (ref "POWER") (pin "A") (pinfunction "A_A") (pintype "passive"))
      (node (ref "U$3") (pin "3") (pinfunction "DRV_3") (pintype "bidirectional"))
    )
    (net (code "17") (name "Net-(C5-P$1)") (class "Default")
      (node (ref "C5") (pin "1") (pinfunction "P$1_1") (pintype "passive"))
      (node (ref "U4") (pin "2") (pinfunction "CAP_2") (pintype "power_in"))
    )
    (net (code "18") (name "Net-(C9-P$2)") (class "Default")
      (node (ref "C9") (pin "2") (pinfunction "P$2_2") (pintype "passive"))
      (node (ref "D3") (pin "1") (pinfunction "1_1") (pintype "passive"))
      (node (ref "J3") (pin "1") (pinfunction "2_1") (pintype "passive"))
      (node (ref "U6") (pin "P$6") (pinfunction "BAT_P$6") (pintype "power_in"))
      (node (ref "U6") (pin "P$8") (pinfunction "SRP_P$8") (pintype "bidirectional"))
    )
    (net (code "19") (name "Net-(C10-P$1)") (class "Default")
      (node (ref "C10") (pin "1") (pinfunction "P$1_1") (pintype "passive"))
      (node (ref "U6") (pin "P$5") (pinfunction "VDD_P$5") (pintype "power_in"))
    )
    (net (code "20") (name "Net-(C11-P$1)") (class "Default")
      (node (ref "C11") (pin "1") (pinfunction "P$1_1") (pintype "passive"))
      (node (ref "D1") (pin "2") (pinfunction "2_2") (pintype "passive"))
      (node (ref "D6") (pin "2") (pinfunction "2_2") (pintype "passive"))
      (node (ref "D9") (pin "1") (pinfunction "1_1") (pintype "passive"))
    )
    (net (code "21") (name "Net-(C12-P$1)") (class "Default")
      (node (ref "C12") (pin "1") (pinfunction "P$1_1") (pintype "passive"))
      (node (ref "U$3") (pin "1") (pinfunction "PMID_1") (pintype "bidirectional"))
    )
    (net (code "22") (name "Net-(C13-P$1)") (class "Default")
      (node (ref "C13") (pin "1") (pinfunction "P$1_1") (pintype "passive"))
      (node (ref "L2") (pin "2") (pinfunction "2_2") (pintype "passive"))
      (node (ref "U$3") (pin "23") (pinfunction "SW1_23") (pintype "bidirectional"))
      (node (ref "U$3") (pin "24") (pinfunction "SW2_24") (pintype "bidirectional"))
    )
    (net (code "23") (name "Net-(C13-P$2)") (class "Default")
      (node (ref "C13") (pin "2") (pinfunction "P$2_2") (pintype "passive"))
      (node (ref "U$3") (pin "2") (pinfunction "BOOT_2") (pintype "bidirectional"))
    )
    (net (code "24") (name "Net-(C15-P$1)") (class "Default")
      (node (ref "C15") (pin "1") (pinfunction "P$1_1") (pintype "passive"))
      (node (ref "D10") (pin "1") (pinfunction "1_1") (pintype "passive"))
      (node (ref "D7") (pin "2") (pinfunction "2_2") (pintype "passive"))
      (node (ref "D8") (pin "2") (pinfunction "2_2") (pintype "passive"))
    )
    (net (code "25") (name "Net-(C16-Pad1)") (class "Default")
      (node (ref "C16") (pin "1") (pinfunction "1_1") (pintype "passive"))
      (node (ref "U2") (pin "24") (pinfunction "24_24") (pintype "bidirectional"))
    )
    (net (code "26") (name "Net-(C16-Pad2)") (class "Default")
      (node (ref "C16") (pin "2") (pinfunction "2_2") (pintype "passive"))
      (node (ref "U2") (pin "23") (pinfunction "23_23") (pintype "bidirectional"))
    )
    (net (code "27") (name "Net-(C17-Pad1)") (class "Default")
      (node (ref "C17") (pin "1") (pinfunction "1_1") (pintype "passive"))
      (node (ref "U2") (pin "21") (pinfunction "21_21") (pintype "power_in"))
    )
    (net (code "28") (name "Net-(C23-Pad1)") (class "Default")
      (node (ref "C23") (pin "1") (pinfunction "1_1") (pintype "passive"))
      (node (ref "C24") (pin "2") (pinfunction "2_2") (pintype "passive"))
      (node (ref "L1") (pin "1") (pinfunction "1_1") (pintype "passive"))
    )
    (net (code "29") (name "Net-(C23-Pad2)") (class "Default")
      (node (ref "C23") (pin "2") (pinfunction "2_2") (pintype "passive"))
      (node (ref "C32") (pin "2") (pinfunction "2_2") (pintype "passive"))
      (node (ref "L1") (pin "2") (pinfunction "2_2") (pintype "passive"))
      (node (ref "L3") (pin "1") (pinfunction "1_1") (pintype "passive"))
    )
    (net (code "30") (name "Net-(C24-Pad1)") (class "Default")
      (node (ref "C24") (pin "1") (pinfunction "1_1") (pintype "passive"))
      (node (ref "L5") (pin "1") (pinfunction "1_1") (pintype "passive"))
      (node (ref "U2") (pin "17") (pinfunction "17_17") (pintype "bidirectional"))
    )
    (net (code "31") (name "Net-(C25-Pad2)") (class "Default")
      (node (ref "C25") (pin "2") (pinfunction "2_2") (pintype "passive"))
      (node (ref "U2") (pin "22") (pinfunction "22_22") (pintype "power_in"))
    )
    (net (code "32") (name "Net-(C28-Pad1)") (class "Default")
      (node (ref "C28") (pin "1") (pinfunction "1_1") (pintype "passive"))
      (node (ref "U2") (pin "6") (pinfunction "6_6") (pintype "power_in"))
    )
    (net (code "33") (name "Net-(C32-Pad1)") (class "Default")
      (node (ref "C32") (pin "1") (pinfunction "1_1") (pintype "passive"))
      (node (ref "L9") (pin "2") (pinfunction "2_2") (pintype "passive"))
      (node (ref "U2") (pin "18") (pinfunction "18_18") (pintype "bidirectional"))
    )
    (net (code "34") (name "Net-(C33-Pad1)") (class "Default")
      (node (ref "C33") (pin "1") (pinfunction "1_1") (pintype "passive"))
      (node (ref "L3") (pin "2") (pinfunction "2_2") (pintype "passive"))
      (node (ref "L4") (pin "1") (pinfunction "1_1") (pintype "passive"))
    )
    (net (code "35") (name "Net-(C34-Pad2)") (class "Default")
      (node (ref "C34") (pin "2") (pinfunction "2_2") (pintype "passive"))
      (node (ref "L5") (pin "2") (pinfunction "2_2") (pintype "passive"))
      (node (ref "R5") (pin "1") (pinfunction "1_1") (pintype "passive"))
    )
    (net (code "36") (name "Net-(C37-Pad1)") (class "Default")
      (node (ref "C37") (pin "1") (pinfunction "1_1") (pintype "passive"))
      (node (ref "L6") (pin "1") (pinfunction "1_1") (pintype "passive"))
      (node (ref "L8") (pin "1") (pinfunction "1_1") (pintype "passive"))
      (node (ref "U2") (pin "19") (pinfunction "19_19") (pintype "bidirectional"))
    )
    (net (code "37") (name "Net-(C37-Pad2)") (class "Default")
      (node (ref "C37") (pin "2") (pinfunction "2_2") (pintype "passive"))
      (node (ref "L7") (pin "2") (pinfunction "2_2") (pintype "passive"))
      (node (ref "L9") (pin "1") (pinfunction "1_1") (pintype "passive"))
    )
    (net (code "38") (name "Net-(C38-Pad1)") (class "Default")
      (node (ref "C38") (pin "1") (pinfunction "1_1") (pintype "passive"))
      (node (ref "L7") (pin "1") (pinfunction "1_1") (pintype "passive"))
      (node (ref "L8") (pin "2") (pinfunction "2_2") (pintype "passive"))
      (node (ref "U2") (pin "20") (pinfunction "20_20") (pintype "bidirectional"))
    )
    (net (code "39") (name "Net-(C46-Pad1)") (class "Default")
      (node (ref "C46") (pin "1") (pinfunction "1_1") (pintype "passive"))
      (node (ref "U1") (pin "67") (pinfunction "67_67") (pintype "power_in"))
    )
    (net (code "40") (name "Net-(C47-Pad1)") (class "Default")
      (node (ref "C47") (pin "1") (pinfunction "1_1") (pintype "passive"))
      (node (ref "U1") (pin "66") (pinfunction "66_66") (pintype "power_in"))
    )
    (net (code "41") (name "Net-(C49-Pad2)") (class "Default")
      (node (ref "C49") (pin "2") (pinfunction "2_2") (pintype "passive"))
      (node (ref "U1") (pin "20") (pinfunction "20_20") (pintype "power_in"))
    )
    (net (code "42") (name "Net-(C53-Pad1)") (class "Default")
      (node (ref "C53") (pin "1") (pinfunction "1_1") (pintype "passive"))
      (node (ref "R28") (pin "1") (pinfunction "1_1") (pintype "passive"))
      (node (ref "U1") (pin "11") (pinfunction "11_11") (pintype "power_in"))
    )
    (net (code "43") (name "Net-(CHARGE-PadC)") (class "Default")
      (node (ref "CHARGE") (pin "C") (pinfunction "C_C") (pintype "passive"))
      (node (ref "R2") (pin "1") (pinfunction "1_1") (pintype "passive"))
    )
    (net (code "44") (name "Net-(CN4-PadGND)") (class "Default")
      (node (ref "CN4") (pin "GND") (pinfunction "GND_GND") (pintype "power_in"))
      (node (ref "R9") (pin "1") (pinfunction "1_1") (pintype "passive"))
    )
    (net (code "45") (name "Net-(G1-PadC)") (class "Default")
      (node (ref "G1") (pin "C") (pinfunction "C_C") (pintype "passive"))
      (node (ref "R10") (pin "2") (pinfunction "2_2") (pintype "passive"))
    )
    (net (code "46") (name "Net-(J$1-SIGNAL)") (class "Default")
      (node (ref "J$1") (pin "SIG") (pinfunction "SIGNAL_SIG") (pintype "bidirectional"))
      (node (ref "R1") (pin "2") (pinfunction "2_2") (pintype "passive"))
    )
    (net (code "47") (name "Net-(L4-Pad2)") (class "Default")
      (node (ref "L4") (pin "2") (pinfunction "2_2") (pintype "passive"))
      (node (ref "R1") (pin "1") (pinfunction "1_1") (pintype "passive"))
    )
    (net (code "48") (name "Net-(POWER-PadC)") (class "Default")
      (node (ref "POWER") (pin "C") (pinfunction "C_C") (pintype "passive"))
      (node (ref "R3") (pin "1") (pinfunction "1_1") (pintype "passive"))
    )
    (net (code "49") (name "Net-(Q1-X1)") (class "Default")
      (node (ref "C40") (pin "1") (pinfunction "1_1") (pintype "passive"))
      (node (ref "Q1") (pin "1") (pinfunction "X1_1") (pintype "bidirectional"))
      (node (ref "U2") (pin "30") (pinfunction "30_30") (pintype "bidirectional"))
    )
    (net (code "50") (name "Net-(Q1-X2)") (class "Default")
      (node (ref "C39") (pin "1") (pinfunction "1_1") (pintype "passive"))
      (node (ref "Q1") (pin "3") (pinfunction "X2_3") (pintype "bidirectional"))
      (node (ref "U2") (pin "31") (pinfunction "31_31") (pintype "bidirectional"))
    )
    (net (code "51") (name "Net-(Q2-1)") (class "Default")
      (node (ref "C51") (pin "2") (pinfunction "2_2") (pintype "passive"))
      (node (ref "Q2") (pin "P1") (pinfunction "1_P1") (pintype "bidirectional"))
      (node (ref "U1") (pin "13") (pinfunction "13_13") (pintype "bidirectional"))
    )
    (net (code "52") (name "Net-(Q2-2)") (class "Default")
      (node (ref "C52") (pin "2") (pinfunction "2_2") (pintype "passive"))
      (node (ref "Q2") (pin "P2") (pinfunction "2_P2") (pintype "bidirectional"))
      (node (ref "U1") (pin "12") (pinfunction "12_12") (pintype "bidirectional"))
    )
    (net (code "53") (name "Net-(Q4-Pad1)") (class "Default")
      (node (ref "Q4") (pin "1") (pinfunction "1_1") (pintype "passive"))
      (node (ref "U1") (pin "70") (pinfunction "70_70") (pintype "bidirectional"))
    )
    (net (code "54") (name "Net-(Q4-Pad3)") (class "Default")
      (node (ref "Q4") (pin "3") (pinfunction "3_3") (pintype "passive"))
      (node (ref "U1") (pin "69") (pinfunction "69_69") (pintype "bidirectional"))
    )
    (net (code "55") (name "Net-(R6-Pad1)") (class "Default")
      (node (ref "R6") (pin "1") (pinfunction "1_1") (pintype "passive"))
      (node (ref "U2") (pin "14") (pinfunction "14_14") (pintype "power_in"))
    )
    (net (code "56") (name "Net-(S5-S)") (class "Default")
      (node (ref "R14") (pin "1") (pinfunction "1_1") (pintype "passive"))
      (node (ref "S5") (pin "2") (pinfunction "S_2") (pintype "passive"))
    )
    (net (code "57") (name "Net-(U$3-STAT)") (class "Default")
      (node (ref "R2") (pin "2") (pinfunction "2_2") (pintype "passive"))
      (node (ref "U$3") (pin "13") (pinfunction "STAT_13") (pintype "bidirectional"))
    )
    (net (code "58") (name "Net-(U6-PROG)") (class "Default")
      (node (ref "D5") (pin "1") (pinfunction "1_1") (pintype "passive"))
      (node (ref "JP2") (pin "1") (pinfunction "1_1") (pintype "passive"))
      (node (ref "U6") (pin "P$12") (pinfunction "PROG_P$12") (pintype "bidirectional"))
    )
    (net (code "59") (name "Net-(U6-TEST)") (class "Default")
      (node (ref "D4") (pin "1") (pinfunction "1_1") (pintype "passive"))
      (node (ref "U6") (pin "P$10") (pinfunction "TEST_P$10") (pintype "bidirectional"))
    )
    (net (code "60") (name "Net-(U7-IO1)") (class "Default")
      (node (ref "CN4") (pin "D+") (pinfunction "D+_D+") (pintype "bidirectional"))
      (node (ref "R7") (pin "1") (pinfunction "1_1") (pintype "passive"))
      (node (ref "U7") (pin "3") (pinfunction "IO1_3") (pintype "bidirectional"))
    )
    (net (code "61") (name "Net-(U7-IO2)") (class "Default")
      (node (ref "CN4") (pin "D-") (pinfunction "D-_D-") (pintype "bidirectional"))
      (node (ref "R8") (pin "1") (pinfunction "1_1") (pintype "passive"))
      (node (ref "U7") (pin "5") (pinfunction "IO2_5") (pintype "bidirectional"))
    )
    (net (code "62") (name "Net-(U7-VCC)") (class "Default")
      (node (ref "CN4") (pin "VBUS") (pinfunction "VBUS_VBUS") (pintype "power_in"))
      (node (ref "D11") (pin "A") (pinfunction "A_A") (pintype "passive"))
      (node (ref "U7") (pin "1") (pinfunction "VCC_1") (pintype "power_in"))
    )
    (net (code "63") (name "Net-(U8-BP)") (class "Default")
      (node (ref "C41") (pin "1") (pinfunction "1_1") (pintype "passive"))
      (node (ref "U8") (pin "4") (pinfunction "BP_4") (pintype "input"))
    )
    (net (code "64") (name "Net-(U8-OUT)") (class "Default")
      (node (ref "C45") (pin "2") (pinfunction "2_2") (pintype "passive"))
      (node (ref "U8") (pin "5") (pinfunction "OUT_5") (pintype "passive"))
    )
    (net (code "65") (name "P1.0") (class "Default")
      (node (ref "J5") (pin "15") (pinfunction "15_15") (pintype "passive"))
      (node (ref "U1") (pin "21") (pinfunction "21_21") (pintype "bidirectional"))
    )
    (net (code "66") (name "P1.1") (class "Default")
      (node (ref "J5") (pin "13") (pinfunction "13_13") (pintype "passive"))
      (node (ref "U1") (pin "22") (pinfunction "22_22") (pintype "bidirectional"))
    )
    (net (code "67") (name "P1.2") (class "Default")
      (node (ref "J5") (pin "11") (pinfunction "11_11") (pintype "passive"))
      (node (ref "U1") (pin "23") (pinfunction "23_23") (pintype "bidirectional"))
    )
    (net (code "68") (name "P1.3") (class "Default")
      (node (ref "J5") (pin "9") (pinfunction "9_9") (pintype "passive"))
      (node (ref "U1") (pin "24") (pinfunction "24_24") (pintype "bidirectional"))
    )
    (net (code "69") (name "P1.4") (class "Default")
      (node (ref "J5") (pin "7") (pinfunction "7_7") (pintype "passive"))
      (node (ref "U1") (pin "25") (pinfunction "25_25") (pintype "bidirectional"))
    )
    (net (code "70") (name "P1.5") (class "Default")
      (node (ref "J5") (pin "5") (pinfunction "5_5") (pintype "passive"))
      (node (ref "U1") (pin "26") (pinfunction "26_26") (pintype "bidirectional"))
    )
    (net (code "71") (name "P1.6") (class "Default")
      (node (ref "J1") (pin "9") (pinfunction "9_9") (pintype "passive"))
      (node (ref "J5") (pin "3") (pinfunction "3_3") (pintype "passive"))
      (node (ref "U1") (pin "27") (pinfunction "27_27") (pintype "bidirectional"))
    )
    (net (code "72") (name "P1.7") (class "Default")
      (node (ref "J5") (pin "1") (pinfunction "1_1") (pintype "passive"))
      (node (ref "U1") (pin "28") (pinfunction "28_28") (pintype "bidirectional"))
    )
    (net (code "73") (name "P2.0") (class "Default")
      (node (ref "J1") (pin "13") (pinfunction "13_13") (pintype "passive"))
      (node (ref "U1") (pin "29") (pinfunction "29_29") (pintype "bidirectional"))
    )
    (net (code "74") (name "P2.1") (class "Default")
      (node (ref "J1") (pin "15") (pinfunction "15_15") (pintype "passive"))
      (node (ref "U1") (pin "30") (pinfunction "30_30") (pintype "bidirectional"))
    )
    (net (code "75") (name "P2.2") (class "Default")
      (node (ref "J5") (pin "6") (pinfunction "6_6") (pintype "passive"))
      (node (ref "U1") (pin "31") (pinfunction "31_31") (pintype "bidirectional"))
    )
    (net (code "76") (name "P2.3") (class "Default")
      (node (ref "J5") (pin "18") (pinfunction "18_18") (pintype "passive"))
      (node (ref "U1") (pin "32") (pinfunction "32_32") (pintype "bidirectional"))
    )
    (net (code "77") (name "P2.4") (class "Default")
      (node (ref "J1") (pin "17") (pinfunction "17_17") (pintype "passive"))
      (node (ref "U1") (pin "33") (pinfunction "33_33") (pintype "bidirectional"))
    )
    (net (code "78") (name "P2.5") (class "Default")
      (node (ref "J1") (pin "19") (pinfunction "19_19") (pintype "passive"))
      (node (ref "U1") (pin "34") (pinfunction "34_34") (pintype "bidirectional"))
    )
    (net (code "79") (name "P2.6") (class "Default")
      (node (ref "J1") (pin "16") (pinfunction "16_16") (pintype "passive"))
      (node (ref "J5") (pin "16") (pinfunction "16_16") (pintype "passive"))
      (node (ref "U1") (pin "35") (pinfunction "35_35") (pintype "bidirectional"))
    )
    (net (code "80") (name "P3.5") (class "Default")
      (node (ref "J1") (pin "20") (pinfunction "20_20") (pintype "passive"))
      (node (ref "U1") (pin "42") (pinfunction "42_42") (pintype "bidirectional"))
    )
    (net (code "81") (name "P3.6") (class "Default")
      (node (ref "J1") (pin "18") (pinfunction "18_18") (pintype "passive"))
      (node (ref "U1") (pin "43") (pinfunction "43_43") (pintype "bidirectional"))
    )
    (net (code "82") (name "P3.7") (class "Default")
      (node (ref "J5") (pin "17") (pinfunction "17_17") (pintype "passive"))
      (node (ref "U1") (pin "44") (pinfunction "44_44") (pintype "bidirectional"))
    )
    (net (code "83") (name "P5.0") (class "Default")
      (node (ref "J1") (pin "5") (pinfunction "5_5") (pintype "passive"))
      (node (ref "U1") (pin "9") (pinfunction "9_9") (pintype "bidirectional"))
    )
    (net (code "84") (name "P5.1") (class "Default")
      (node (ref "J1") (pin "7") (pinfunction "7_7") (pintype "passive"))
      (node (ref "U1") (pin "10") (pinfunction "10_10") (pintype "bidirectional"))
    )
    (net (code "85") (name "P6.0") (class "Default")
      (node (ref "J1") (pin "6") (pinfunction "6_6") (pintype "passive"))
      (node (ref "U1") (pin "77") (pinfunction "77_77") (pintype "bidirectional"))
    )
    (net (code "86") (name "P6.1") (class "Default")
      (node (ref "J1") (pin "8") (pinfunction "8_8") (pintype "passive"))
      (node (ref "U1") (pin "78") (pinfunction "78_78") (pintype "bidirectional"))
    )
    (net (code "87") (name "P6.2") (class "Default")
      (node (ref "J1") (pin "10") (pinfunction "10_10") (pintype "passive"))
      (node (ref "U1") (pin "79") (pinfunction "79_79") (pintype "bidirectional"))
    )
    (net (code "88") (name "P6.3") (class "Default")
      (node (ref "J1") (pin "12") (pinfunction "12_12") (pintype "passive"))
      (node (ref "U1") (pin "80") (pinfunction "80_80") (pintype "bidirectional"))
    )
    (net (code "89") (name "P6.4") (class "Default")
      (node (ref "J1") (pin "14") (pinfunction "14_14") (pintype "passive"))
      (node (ref "U1") (pin "1") (pinfunction "1_1") (pintype "bidirectional"))
    )
    (net (code "90") (name "P6.5") (class "Default")
      (node (ref "J1") (pin "3") (pinfunction "3_3") (pintype "passive"))
      (node (ref "U1") (pin "2") (pinfunction "2_2") (pintype "bidirectional"))
    )
    (net (code "91") (name "P6.6") (class "Default")
      (node (ref "J1") (pin "11") (pinfunction "11_11") (pintype "passive"))
      (node (ref "U1") (pin "3") (pinfunction "3_3") (pintype "bidirectional"))
    )
    (net (code "92") (name "P6.7") (class "Default")
      (node (ref "J1") (pin "4") (pinfunction "4_4") (pintype "passive"))
      (node (ref "U1") (pin "4") (pinfunction "4_4") (pintype "bidirectional"))
    )
    (net (code "93") (name "P8.1") (class "Default")
      (node (ref "J5") (pin "14") (pinfunction "14_14") (pintype "passive"))
      (node (ref "U1") (pin "16") (pinfunction "16_16") (pintype "bidirectional"))
    )
    (net (code "94") (name "P8.2") (class "Default")
      (node (ref "J5") (pin "19") (pinfunction "19_19") (pintype "passive"))
      (node (ref "U1") (pin "17") (pinfunction "17_17") (pintype "bidirectional"))
    )
    (net (code "95") (name "PRESSURE_INT") (class "Default")
      (node (ref "U1") (pin "59") (pinfunction "59_59") (pintype "bidirectional"))
      (node (ref "U4") (pin "6") (pinfunction "INT1_6") (pintype "output"))
    )
    (net (code "96") (name "PWR_SCL") (class "Default")
      (node (ref "D7") (pin "1") (pinfunction "1_1") (pintype "passive"))
      (node (ref "U$3") (pin "16") (pinfunction "SCL_16") (pintype "bidirectional"))
      (node (ref "U6") (pin "P$2") (pinfunction "SCL_P$2") (pintype "bidirectional"))
    )
    (net (code "97") (name "PWR_SDA") (class "Default")
      (node (ref "D6") (pin "1") (pinfunction "1_1") (pintype "passive"))
      (node (ref "U$3") (pin "17") (pinfunction "SDA_17") (pintype "bidirectional"))
      (node (ref "U6") (pin "P$1") (pinfunction "SDA_P$1") (pintype "bidirectional"))
    )
    (net (code "98") (name "REGULATOR_VCC") (class "Default")
      (node (ref "C45") (pin "1") (pinfunction "1_1") (pintype "passive"))
      (node (ref "S2") (pin "1") (pinfunction "1_1") (pintype "bidirectional"))
      (node (ref "S2") (pin "4") (pinfunction "4_4") (pintype "bidirectional"))
    )
    (net (code "99") (name "RF_CLK") (class "Default")
      (node (ref "U1") (pin "39") (pinfunction "39_39") (pintype "bidirectional"))
      (node (ref "U2") (pin "8") (pinfunction "8_8") (pintype "bidirectional"))
    )
    (net (code "100") (name "RF_CSN") (class "Default")
      (node (ref "U1") (pin "5") (pinfunction "5_5") (pintype "bidirectional"))
      (node (ref "U2") (pin "11") (pinfunction "11_11") (pintype "bidirectional"))
    )
    (net (code "101") (name "RF_GPIO0") (class "Default")
      (node (ref "U1") (pin "7") (pinfunction "7_7") (pintype "bidirectional"))
      (node (ref "U2") (pin "10") (pinfunction "10_10") (pintype "bidirectional"))
    )
    (net (code "102") (name "RF_GPIO2") (class "Default")
      (node (ref "U1") (pin "8") (pinfunction "8_8") (pintype "bidirectional"))
      (node (ref "U2") (pin "4") (pinfunction "4_4") (pintype "bidirectional"))
    )
    (net (code "103") (name "RF_GPIO3") (class "Default")
      (node (ref "U1") (pin "57") (pinfunction "57_57") (pintype "bidirectional"))
      (node (ref "U2") (pin "3") (pinfunction "3_3") (pintype "input"))
    )
    (net (code "104") (name "RF_RESET") (class "Default")
      (node (ref "U1") (pin "6") (pinfunction "6_6") (pintype "bidirectional"))
      (node (ref "U2") (pin "2") (pinfunction "2_2") (pintype "input"))
    )
    (net (code "105") (name "RF_SIMO") (class "Default")
      (node (ref "U1") (pin "37") (pinfunction "37_37") (pintype "bidirectional"))
      (node (ref "U2") (pin "7") (pinfunction "7_7") (pintype "bidirectional"))
    )
    (net (code "106") (name "RF_SOMI") (class "Default")
      (node (ref "U1") (pin "38") (pinfunction "38_38") (pintype "bidirectional"))
      (node (ref "U2") (pin "9") (pinfunction "9_9") (pintype "bidirectional"))
    )
    (net (code "107") (name "RST{slash}SBWTDIO") (class "Default")
      (node (ref "C48") (pin "1") (pinfunction "1_1") (pintype "passive"))
      (node (ref "J2") (pin "11") (pinfunction "11_11") (pintype "passive"))
      (node (ref "J5") (pin "10") (pinfunction "10_10") (pintype "passive"))
      (node (ref "R27") (pin "1") (pinfunction "1_1") (pintype "passive"))
      (node (ref "S3") (pin "2") (pinfunction "S_2") (pintype "passive"))
      (node (ref "U1") (pin "76") (pinfunction "76_76") (pintype "bidirectional"))
    )
    (net (code "108") (name "TCK") (class "Default")
      (node (ref "J2") (pin "7") (pinfunction "7_7") (pintype "passive"))
      (node (ref "U1") (pin "75") (pinfunction "75_75") (pintype "bidirectional"))
    )
    (net (code "109") (name "TDI") (class "Default")
      (node (ref "J2") (pin "3") (pinfunction "3_3") (pintype "passive"))
      (node (ref "U1") (pin "73") (pinfunction "73_73") (pintype "bidirectional"))
    )
    (net (code "110") (name "TDO") (class "Default")
      (node (ref "J2") (pin "1") (pinfunction "1_1") (pintype "passive"))
      (node (ref "U1") (pin "72") (pinfunction "72_72") (pintype "bidirectional"))
    )
    (net (code "111") (name "TEST{slash}SBWTCK") (class "Default")
      (node (ref "J2") (pin "8") (pinfunction "8_8") (pintype "passive"))
      (node (ref "U1") (pin "71") (pinfunction "71_71") (pintype "input"))
    )
    (net (code "112") (name "TMS") (class "Default")
      (node (ref "J2") (pin "5") (pinfunction "5_5") (pintype "passive"))
      (node (ref "U1") (pin "74") (pinfunction "74_74") (pintype "bidirectional"))
    )
    (net (code "113") (name "UCA1_CLK") (class "Default")
      (node (ref "J5") (pin "4") (pinfunction "4_4") (pintype "passive"))
      (node (ref "U1") (pin "45") (pinfunction "45_45") (pintype "bidirectional"))
    )
    (net (code "114") (name "UCA1_RXD") (class "Default")
      (node (ref "J5") (pin "20") (pinfunction "20_20") (pintype "passive"))
      (node (ref "U1") (pin "52") (pinfunction "52_52") (pintype "bidirectional"))
    )
    (net (code "115") (name "UCA1_STE") (class "Default")
      (node (ref "J5") (pin "12") (pinfunction "12_12") (pintype "passive"))
      (node (ref "U1") (pin "48") (pinfunction "48_48") (pintype "bidirectional"))
    )
    (net (code "116") (name "UCA1_TXD") (class "Default")
      (node (ref "J5") (pin "8") (pinfunction "8_8") (pintype "passive"))
      (node (ref "U1") (pin "51") (pinfunction "51_51") (pintype "bidirectional"))
    )
    (net (code "117") (name "USB_DM") (class "Default")
      (node (ref "C42") (pin "1") (pinfunction "P$1_1") (pintype "passive"))
      (node (ref "R8") (pin "2") (pinfunction "2_2") (pintype "passive"))
      (node (ref "U1") (pin "64") (pinfunction "64_64") (pintype "bidirectional"))
    )
    (net (code "118") (name "USB_DP") (class "Default")
      (node (ref "C43") (pin "1") (pinfunction "P$1_1") (pintype "passive"))
      (node (ref "R15") (pin "2") (pinfunction "2_2") (pintype "passive"))
      (node (ref "R7") (pin "2") (pinfunction "2_2") (pintype "passive"))
      (node (ref "U1") (pin "62") (pinfunction "62_62") (pintype "bidirectional"))
    )
    (net (code "119") (name "USB_VBUS") (class "Default")
      (node (ref "C59") (pin "1") (pinfunction "1_1") (pintype "passive"))
      (node (ref "C60") (pin "1") (pinfunction "1_1") (pintype "passive"))
      (node (ref "C8") (pin "1") (pinfunction "P$1_1") (pintype "passive"))
      (node (ref "D11") (pin "C") (pinfunction "C_C") (pintype "passive"))
      (node (ref "J1") (pin "2") (pinfunction "2_2") (pintype "passive"))
      (node (ref "S5") (pin "1") (pinfunction "P_1") (pintype "passive"))
      (node (ref "U$3") (pin "14") (pinfunction "PSEL_14") (pintype "bidirectional"))
      (node (ref "U$3") (pin "18") (pinfunction "IN1_18") (pintype "bidirectional"))
      (node (ref "U$3") (pin "19") (pinfunction "IN2_19") (pintype "bidirectional"))
      (node (ref "U1") (pin "65") (pinfunction "65_65") (pintype "power_in"))
    )
    (net (code "120") (name "VBAT+") (class "Default")
      (node (ref "D3") (pin "2") (pinfunction "2_2") (pintype "passive"))
      (node (ref "U$3") (pin "8") (pinfunction "BAT1_8") (pintype "bidirectional"))
      (node (ref "U$3") (pin "9") (pinfunction "BAT2_9") (pintype "bidirectional"))
      (node (ref "U6") (pin "P$7") (pinfunction "SRN_P$7") (pintype "bidirectional"))
    )
    (net (code "121") (name "VCC") (class "Default")
      (node (ref "C1") (pin "1") (pinfunction "P$1_1") (pintype "passive"))
      (node (ref "C18") (pin "1") (pinfunction "1_1") (pintype "passive"))
      (node (ref "C19") (pin "1") (pinfunction "1_1") (pintype "passive"))
      (node (ref "C2") (pin "1") (pinfunction "P$1_1") (pintype "passive"))
      (node (ref "C20") (pin "1") (pinfunction "1_1") (pintype "passive"))
      (node (ref "C21") (pin "1") (pinfunction "1_1") (pintype "passive"))
      (node (ref "C22") (pin "1") (pinfunction "1_1") (pintype "passive"))
      (node (ref "C25") (pin "1") (pinfunction "1_1") (pintype "passive"))
      (node (ref "C26") (pin "1") (pinfunction "1_1") (pintype "passive"))
      (node (ref "C27") (pin "1") (pinfunction "1_1") (pintype "passive"))
      (node (ref "C29") (pin "1") (pinfunction "1_1") (pintype "passive"))
      (node (ref "C3") (pin "1") (pinfunction "P$1_1") (pintype "passive"))
      (node (ref "C30") (pin "1") (pinfunction "1_1") (pintype "passive"))
      (node (ref "C31") (pin "1") (pinfunction "1_1") (pintype "passive"))
      (node (ref "C34") (pin "1") (pinfunction "1_1") (pintype "passive"))
      (node (ref "C35") (pin "1") (pinfunction "1_1") (pintype "passive"))
      (node (ref "C36") (pin "1") (pinfunction "1_1") (pintype "passive"))
      (node (ref "C44") (pin "1") (pinfunction "1_1") (pintype "passive"))
      (node (ref "C50") (pin "2") (pinfunction "2_2") (pintype "passive"))
      (node (ref "C54") (pin "+") (pinfunction "+_+") (pintype "passive"))
      (node (ref "C55") (pin "+") (pinfunction "+_+") (pintype "passive"))
      (node (ref "C57") (pin "2") (pinfunction "2_2") (pintype "passive"))
      (node (ref "C7") (pin "1") (pinfunction "P$1_1") (pintype "passive"))
      (node (ref "J1") (pin "1") (pinfunction "1_1") (pintype "passive"))
      (node (ref "JP1") (pin "3") (pinfunction "3_3") (pintype "passive"))
      (node (ref "R27") (pin "2") (pinfunction "2_2") (pintype "passive"))
      (node (ref "R28") (pin "2") (pinfunction "2_2") (pintype "passive"))
      (node (ref "R4") (pin "2") (pinfunction "2_2") (pintype "passive"))
      (node (ref "R5") (pin "2") (pinfunction "2_2") (pintype "passive"))
      (node (ref "S2") (pin "2") (pinfunction "2_2") (pintype "bidirectional"))
      (node (ref "U1") (pin "18") (pinfunction "18_18") (pintype "power_in"))
      (node (ref "U1") (pin "50") (pinfunction "50_50") (pintype "power_in"))
      (node (ref "U2") (pin "1") (pinfunction "1_1") (pintype "power_in"))
      (node (ref "U2") (pin "12") (pinfunction "12_12") (pintype "power_in"))
      (node (ref "U2") (pin "13") (pinfunction "13_13") (pintype "power_in"))
      (node (ref "U2") (pin "15") (pinfunction "15_15") (pintype "power_in"))
      (node (ref "U2") (pin "25") (pinfunction "25_25") (pintype "power_in"))
      (node (ref "U2") (pin "26") (pinfunction "26_26") (pintype "power_in"))
      (node (ref "U2") (pin "27") (pinfunction "27_27") (pintype "power_in"))
      (node (ref "U2") (pin "28") (pinfunction "28_28") (pintype "power_in"))
      (node (ref "U2") (pin "29") (pinfunction "29_29") (pintype "input"))
      (node (ref "U2") (pin "5") (pinfunction "5_5") (pintype "power_in"))
      (node (ref "U2") (pin "TP") (pinfunction "33_TP") (pintype "power_in"))
      (node (ref "U3") (pin "VDD") (pinfunction "VDD_VDD") (pintype "power_in"))
      (node (ref "U4") (pin "1") (pinfunction "VDD_1") (pintype "power_in"))
      (node (ref "U4") (pin "4") (pinfunction "VDDIO_4") (pintype "power_in"))
      (node (ref "U5") (pin "1") (pinfunction "VDD_1") (pintype "power_in"))
      (node (ref "U9") (pin "4") (pinfunction "VCC_4") (pintype "bidirectional"))
    )
    (net (code "122") (name "VOUT_CHRG") (class "Default")
      (node (ref "C14") (pin "1") (pinfunction "P$1_1") (pintype "passive"))
      (node (ref "C6") (pin "1") (pinfunction "1_1") (pintype "passive"))
      (node (ref "L2") (pin "1") (pinfunction "1_1") (pintype "passive"))
      (node (ref "U$3") (pin "6") (pinfunction "SYS1_6") (pintype "bidirectional"))
      (node (ref "U$3") (pin "7") (pinfunction "SYS2_7") (pintype "bidirectional"))
      (node (ref "U8") (pin "1") (pinfunction "IN_1") (pintype "input"))
      (node (ref "U8") (pin "3") (pinfunction "EN_3") (pintype "input"))
    )
    (net (code "123") (name "unconnected-(CN4-PadID)") (class "Default")
      (node (ref "CN4") (pin "ID") (pinfunction "ID_ID") (pintype "bidirectional"))
    )
    (net (code "124") (name "unconnected-(J2-Pad6)") (class "Default")
      (node (ref "J2") (pin "6") (pinfunction "6_6") (pintype "passive"))
    )
    (net (code "125") (name "unconnected-(J2-Pad10)") (class "Default")
      (node (ref "J2") (pin "10") (pinfunction "10_10") (pintype "passive"))
    )
    (net (code "126") (name "unconnected-(J2-Pad12)") (class "Default")
      (node (ref "J2") (pin "12") (pinfunction "12_12") (pintype "passive"))
    )
    (net (code "127") (name "unconnected-(J2-Pad13)") (class "Default")
      (node (ref "J2") (pin "13") (pinfunction "13_13") (pintype "passive"))
    )
    (net (code "128") (name "unconnected-(J2-Pad14)") (class "Default")
      (node (ref "J2") (pin "14") (pinfunction "14_14") (pintype "passive"))
    )
    (net (code "129") (name "unconnected-(S2-Pad6)") (class "Default")
      (node (ref "S2") (pin "6") (pinfunction "6_6") (pintype "bidirectional"))
    )
    (net (code "130") (name "unconnected-(U$3-BGATE-Pad11)") (class "Default")
      (node (ref "U$3") (pin "11") (pinfunction "BGATE_11") (pintype "bidirectional"))
    )
    (net (code "131") (name "unconnected-(U$3-NC-Pad15)") (class "Default")
      (node (ref "U$3") (pin "15") (pinfunction "NC_15") (pintype "bidirectional"))
    )
    (net (code "132") (name "unconnected-(U1-Pad15)") (class "Default")
      (node (ref "U1") (pin "15") (pinfunction "15_15") (pintype "bidirectional"))
    )
    (net (code "133") (name "unconnected-(U1-Pad54)") (class "Default")
      (node (ref "U1") (pin "54") (pinfunction "54_54") (pintype "bidirectional"))
    )
    (net (code "134") (name "unconnected-(U2-Pad16)") (class "Default")
      (node (ref "U2") (pin "16") (pinfunction "16_16") (pintype "no_connect"))
    )
    (net (code "135") (name "unconnected-(U2-Pad32)") (class "Default")
      (node (ref "U2") (pin "32") (pinfunction "32_32") (pintype "bidirectional"))
    )
    (net (code "136") (name "unconnected-(U4-INT2-Pad5)") (class "Default")
      (node (ref "U4") (pin "5") (pinfunction "INT2_5") (pintype "output"))
    )
    (net (code "137") (name "unconnected-(U6-NC1-PadP$4)") (class "Default")
      (node (ref "U6") (pin "P$4") (pinfunction "NC1_P$4") (pintype "no_connect"))
    )
    (net (code "138") (name "unconnected-(U6-NC2-PadP$9)") (class "Default")
      (node (ref "U6") (pin "P$9") (pinfunction "NC2_P$9") (pintype "no_connect"))
    )
    (net (code "139") (name "unconnected-(U6-NC3-PadP$11)") (class "Default")
      (node (ref "U6") (pin "P$11") (pinfunction "NC3_P$11") (pintype "no_connect"))
    )
    (net (code "140") (name "unconnected-(U7-NC-Pad2)") (class "Default")
      (node (ref "U7") (pin "2") (pinfunction "NC_2") (pintype "no_connect"))
    )
    (net (code "141") (name "unconnected-(U9-NC-Pad1)") (class "Default")
      (node (ref "U9") (pin "1") (pinfunction "NC_1") (pintype "bidirectional"))
    )
    (net (code "142") (name "unconnected-(U9-RSV-Pad8)") (class "Default")
      (node (ref "U9") (pin "8") (pinfunction "RSV_8") (pintype "bidirectional"))
    )
    (net (code "143") (name "unconnected-(U9-SHIELD-PadCD2)") (class "Default")
      (node (ref "U9") (pin "CD2") (pinfunction "SHIELD_CD2") (pintype "bidirectional"))
    )
  )
)
